# 03_MSP430_AFE.net
KiCad netlist of a schematic drawn in Altium Designer
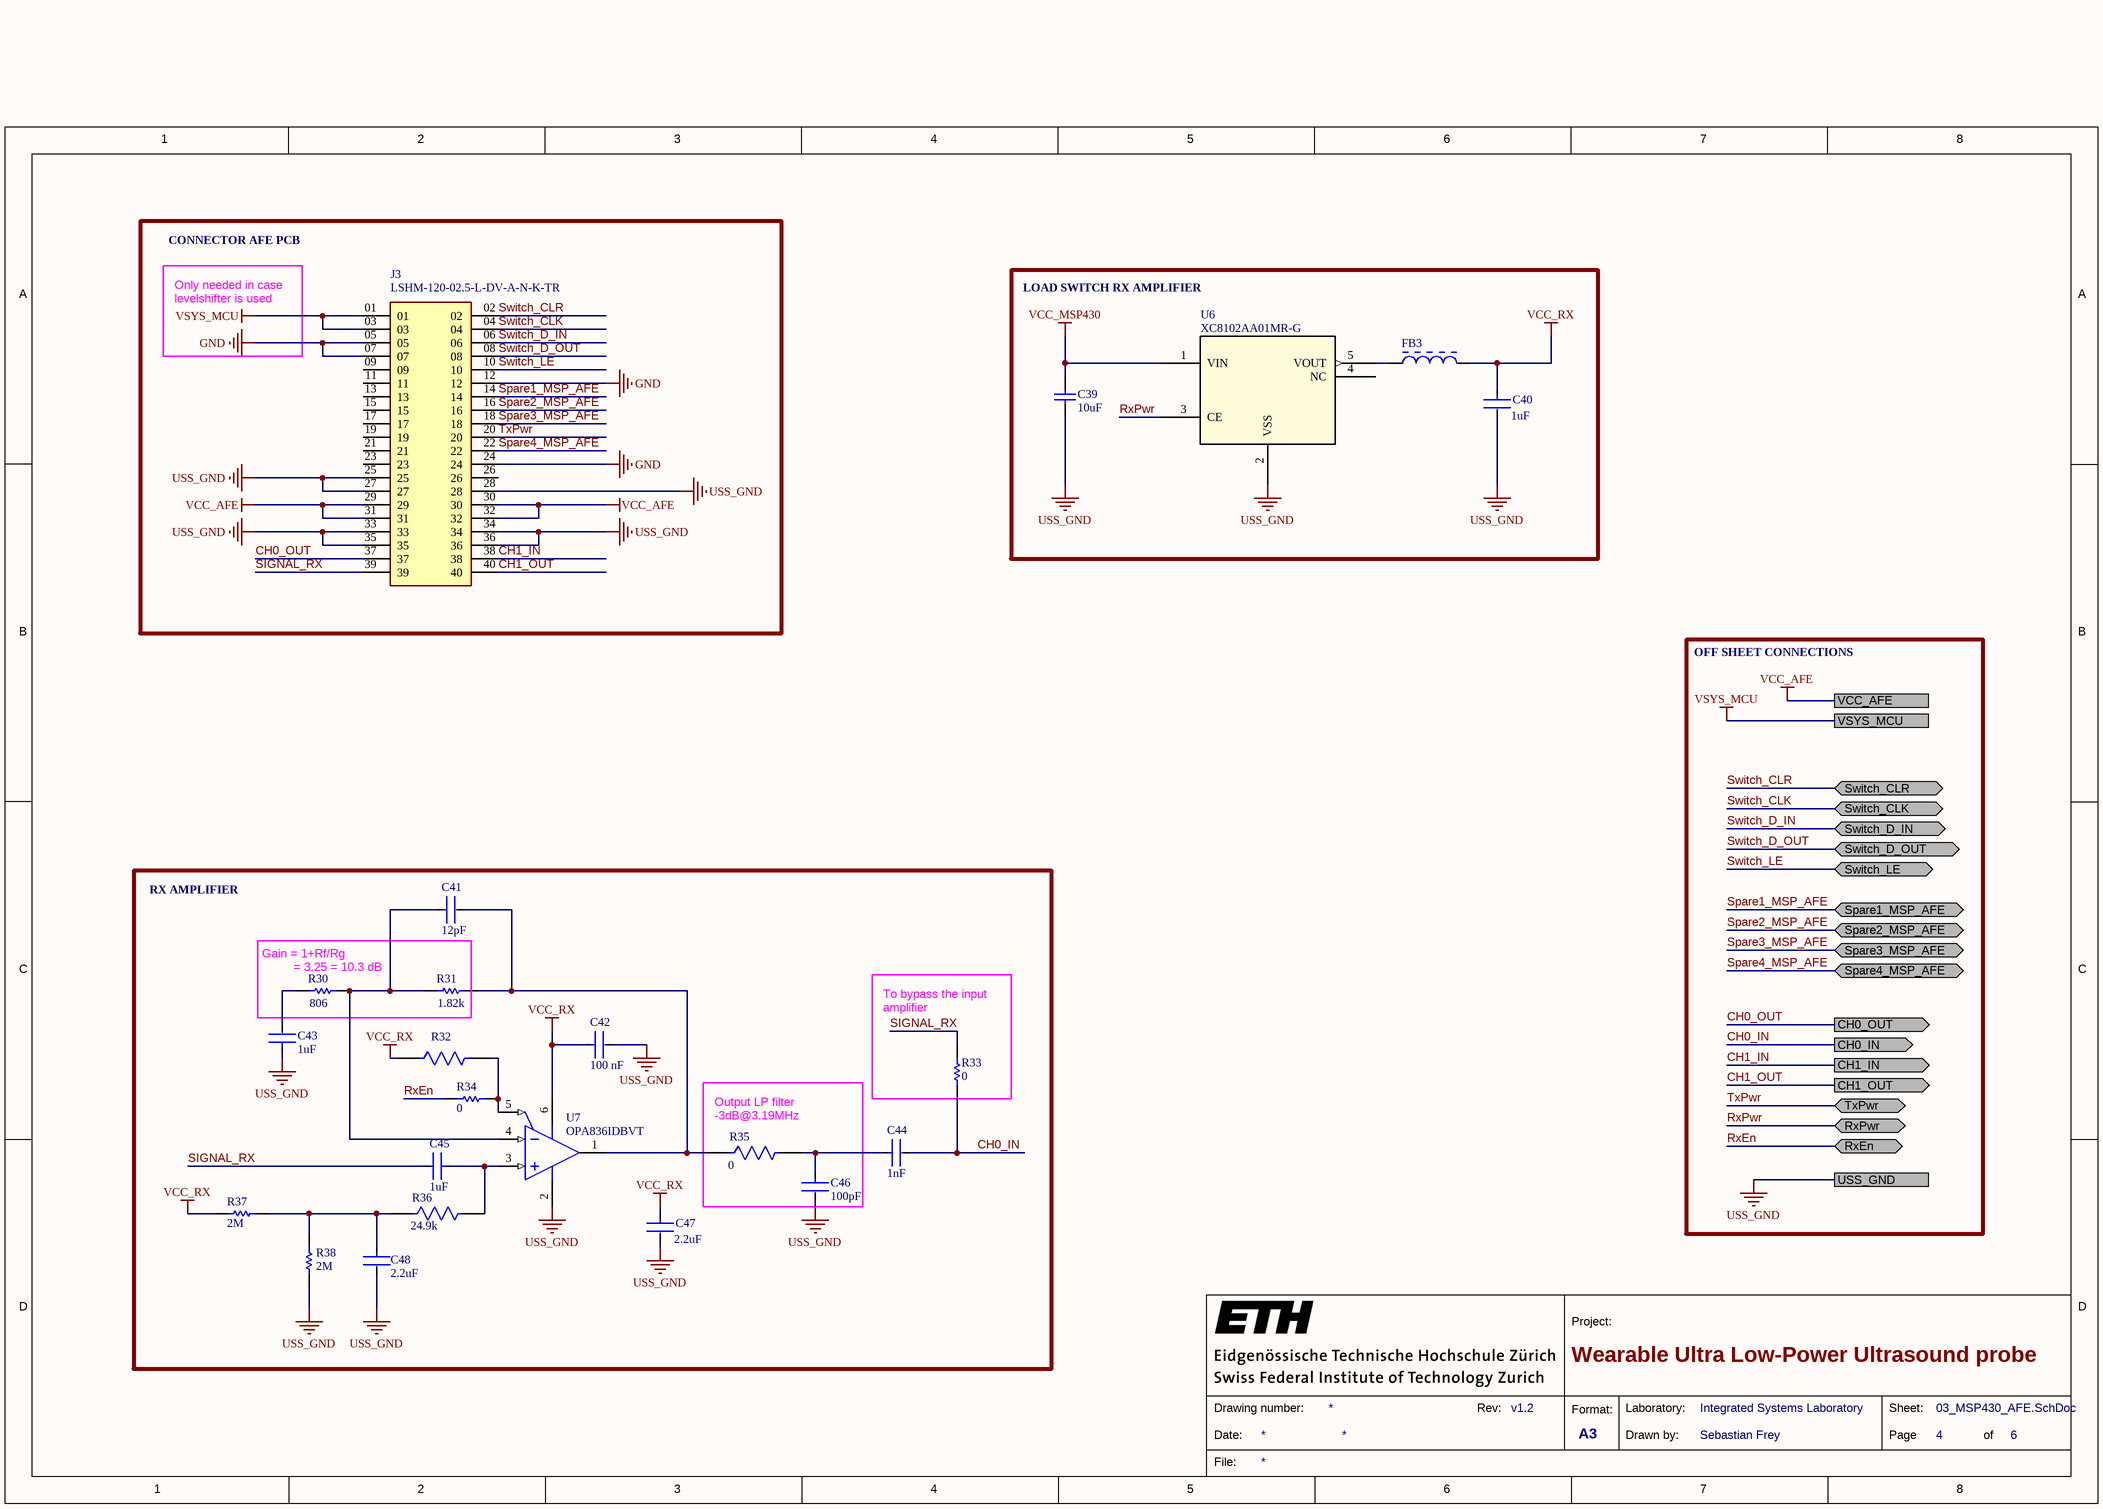
[diagram p0: 03_MSP430_AFE.SchDoc]

(export (version "E")
  (design (tool "Eeschema 10.0.6"))
  (components
    (comp (ref "C39")
      (value "10uF")
      (footprint "CAPC0603(1608)100_L")
      (description "CAP 10uF 10V ±10% 0603 (1608 Metric) Thickness 1mm SMD")
      (fields (field (name "TOLERANCE") "Â±10%") (field (name "Comment") "C1608X5R1A106K080AC"))
      (libsource (lib "Altium Content Vault") (part "CMP-1035-02799-1"))
    )
    (comp (ref "C40")
      (value "C1608X7R1C105K080AC")
      (footprint "FP-C1608-080-0_1-IPC_B")
      (description "Multilayer Ceramic Capacitors 1μF ±10% 16V X7R SMD 0603")
      (fields
        (field (name "VOLTAGE") "16V")
        (field (name "CAPACITANCE") "1uF")
        (field (name "TOLERANCE") "10%")
      )
      (libsource (lib "Altium Content Vault") (part "236180d848d6139a670b325ea6854c9"))
    )
    (comp (ref "C41")
      (value "GJM1555C1H120GB01D")
      (footprint "FP-GJM155-0_05-IPC_A")
      (description "Multi-Layer Ceramic Capacitor 12pF C0G  ±2% 0402 Paper T/R")
      (fields (field (name "TOLERANCE") "2%") (field (name "CAPACITANCE") "12pF"))
      (libsource (lib "Altium Content Vault") (part "02cd4be3c70576c341d710602a673aa"))
    )
    (comp (ref "C42")
      (value "100 nF")
      (footprint "FP-CC0402-MFG")
      (description "CAP CER 0.1UF 16V X7R 0402")
      (fields (field (name "MANUFACTURER") "YAGEO") (field (name "TOLERANCE") "0.1"))
      (libsource (lib "Altium Content Vault") (part "11868f565c42a9108669ba33697ecf6"))
    )
    (comp (ref "C43")
      (value "C1608X7R1C105K080AC")
      (footprint "FP-C1608-080-0_1-IPC_B")
      (description "Multilayer Ceramic Capacitors 1μF ±10% 16V X7R SMD 0603")
      (fields
        (field (name "VOLTAGE") "16V")
        (field (name "CAPACITANCE") "1uF")
        (field (name "TOLERANCE") "10%")
      )
      (libsource (lib "Altium Content Vault") (part "236180d848d6139a670b325ea6854c9"))
    )
    (comp (ref "C44")
      (value "GRM1555C1H102JA01D")
      (footprint "FP-GRM155-0_05-IPC_B")
      (description "Chip Multilayer Ceramic Capacitors for General Purpose, 0402, 1000pF, C0G, 30ppm/°C, 5%, 50V")
      (fields
        (field (name "TOLERANCE") "5%")
        (field (name "VOLTAGE") "50V")
        (field (name "CAPACITANCE") "1nF")
      )
      (libsource (lib "Altium Content Vault") (part "02cd4be3c70576c341d710602a673aa"))
    )
    (comp (ref "C45")
      (value "C1608X7R1C105K080AC")
      (footprint "FP-C1608-080-0_1-IPC_B")
      (description "Multilayer Ceramic Capacitors 1μF ±10% 16V X7R SMD 0603")
      (fields
        (field (name "VOLTAGE") "16V")
        (field (name "CAPACITANCE") "1uF")
        (field (name "TOLERANCE") "10%")
      )
      (libsource (lib "Altium Content Vault") (part "236180d848d6139a670b325ea6854c9"))
    )
    (comp (ref "C46")
      (value "04025A101JAT2A")
      (footprint "FP-04025A101JAT2A-MFG")
      (description "CAP CER 100PF 50V C0G/NP0 0402")
      (fields
        (field (name "TOLERANCE") "5%")
        (field (name "VOLTAGE") "50V")
        (field (name "CAPACITANCE") "100pF")
      )
      (libsource (lib "Altium Content Vault") (part "f23184f103b6ebe33a8c269c53dcba6"))
    )
    (comp (ref "C47")
      (value "GRM188R61C225KE15D")
      (footprint "FP-CGA3E-0_3-0_1-MFG")
      (description "Cap Ceramic 2.2uF 16V X5R 10% Pad SMD 0603 +85°C Automotive T/R")
      (fields (field (name "TOLERANCE") "10%") (field (name "CAPACITANCE") "2.2uF"))
      (libsource (lib "Altium Content Vault") (part "b4654b650e69147ec39a6b967a45e02"))
    )
    (comp (ref "C48")
      (value "GRM188R61C225KE15D")
      (footprint "FP-CGA3E-0_3-0_1-MFG")
      (description "Cap Ceramic 2.2uF 16V X5R 10% Pad SMD 0603 +85°C Automotive T/R")
      (fields (field (name "TOLERANCE") "10%") (field (name "CAPACITANCE") "2.2uF"))
      (libsource (lib "Altium Content Vault") (part "b4654b650e69147ec39a6b967a45e02"))
    )
    (comp (ref "FB3")
      (value "BLM03AX800SN1D")
      (footprint "MURA-BLM03-CHIP-2_V")
      (fields (field (name "MANUFACTURER") "Murata") (field (name "TOLERANCE") "25%"))
      (libsource (lib "Altium Content Vault") (part "MURA-FB-2"))
    )
    (comp (ref "J3")
      (value "LSHM-120-02.5-L-DV-A-N-K-TR")
      (footprint "PcbLib1:SAMTEC_LSHM-120-XX.X-X-DV-A-N-XX")
      (description "Conn Socket and Terminal Strip HDR/SKT 40 POS 0.5mm Solder ST SMD T/R")
      (fields
        (field (name "MANUFACTURER") "Samtec")
        (field (name "MANUFACTURER PART NUMBER") "LSHM-120-02.5-L-DV-A-N-K-TR")
      )
      (libsource (lib "Schlib1") (part "LSHM-120-02.5-L-DV-A-N-K-TR"))
    )
    (comp (ref "R30")
      (value "RC0603FR-07806RL")
      (footprint "RESC1608X55X25LL10T15")
      (fields (field (name "MANUFACTURER") "Yageo") (field (name "RESISTANCE") "806"))
      (libsource (lib "Altium Content Vault") (part "RES"))
    )
    (comp (ref "R31")
      (value "RC0603FR-071K82L")
      (footprint "RESC1608X55X25ML10T15")
      (fields (field (name "MANUFACTURER") "Yageo") (field (name "RESISTANCE") "1.82k"))
      (libsource (lib "Altium Content Vault") (part "RES"))
    )
    (comp (ref "R32")
      (value "TNPW040210K0BEED")
      (footprint "FP-TNPW0402-e3-MFG")
      (description "RES 10K OHM 0.1% 1/10W 0402")
      (fields
        (field (name "TOLERANCE") "0.1%")
        (field (name "OCTOPART") "https://octopart.com/tnpw040210k0beed-vishay-41229038")
      )
      (libsource (lib "Altium Content Vault") (part "1029c3af85768c4190bb7ad29bc67b5"))
    )
    (comp (ref "R33")
      (value "RC0402JR-070RL")
      (footprint "RESC1005X40X25NL05T10")
      (fields (field (name "MANUFACTURER") "Yageo / Phycomp") (field (name "RESISTANCE") "0"))
      (libsource (lib "Altium Content Vault") (part "RES"))
    )
    (comp (ref "R34")
      (value "RC0402JR-070RL")
      (footprint "RESC1005X40X25NL05T10")
      (fields (field (name "MANUFACTURER") "Yageo / Phycomp") (field (name "RESISTANCE") "0"))
      (libsource (lib "Altium Content Vault") (part "RES"))
    )
    (comp (ref "R35")
      (value "CR0402-J/-000GLF")
      (footprint "FP-CR0402-IPC_B")
      (description "Thick Film Chip Resistors 0402 0Ω 0.0625W 5%")
      (fields (field (name "TOLERANCE") "5%") (field (name "RESISTANCE") "0"))
      (libsource (lib "Altium Content Vault") (part "1029c3af85768c4190bb7ad29bc67b5"))
    )
    (comp (ref "R36")
      (value "RC0603FR-0724K9L")
      (footprint "FP-RC_L0603-MFG")
      (description "RES SMD 24.9K OHM 1% 1/10W 0603")
      (fields
        (field (name "VOLTAGE") "75V")
        (field (name "MANUFACTURER") "Yageo")
        (field (name "RESISTANCE") "24.9k")
      )
      (libsource (lib "Altium Content Vault") (part "1029c3af85768c4190bb7ad29bc67b5"))
    )
    (comp (ref "R37")
      (value "RC0603FR-072ML")
      (footprint "RESC1608X55X30LL15T15")
      (fields (field (name "MANUFACTURER") "YAEGO") (field (name "PARAMETER 1") "2M"))
      (libsource (lib "Altium Content Vault") (part "RES"))
    )
    (comp (ref "R38")
      (value "RC0603FR-072ML")
      (footprint "RESC1608X55X30LL15T15")
      (fields (field (name "MANUFACTURER") "YAEGO") (field (name "PARAMETER 1") "2M"))
      (libsource (lib "Altium Content Vault") (part "RES"))
    )
    (comp (ref "U6")
      (value "XC8102AA01MR-G")
      (footprint "PcbLib1:XC8102_SOT-25_TOR")
      (description "No Description Available")
      (fields (field (name "COPYRIGHT") "Copyright (C) 2021 Ultra Librarian. All rights reserved."))
      (libsource (lib "Schlib1") (part "XC8102AA01MR-G"))
    )
    (comp (ref "U7")
      (value "OPA836IDBVT")
      (footprint "DBV0006A_L")
      (fields (field (name "MANUFACTURER") "Texas Instruments"))
      (libsource (lib "Altium Content Vault") (part "TI-OPA83XDBV6"))
    )
  )
  (nets
    (net (code "1") (name "/CH0_IN") (class "Default")
      (node (ref "C44") (pin "2") (pinfunction "2_2") (pintype "passive"))
      (node (ref "R33") (pin "1") (pinfunction "1_1") (pintype "passive"))
    )
    (net (code "2") (name "/CH0_OUT") (class "Default")
      (node (ref "J3") (pin "37") (pinfunction "37_37") (pintype "passive"))
    )
    (net (code "3") (name "/CH1_IN") (class "Default")
      (node (ref "J3") (pin "38") (pinfunction "38_38") (pintype "passive"))
    )
    (net (code "4") (name "/CH1_OUT") (class "Default")
      (node (ref "J3") (pin "40") (pinfunction "40_40") (pintype "passive"))
    )
    (net (code "5") (name "/RxEn") (class "Default")
      (node (ref "R34") (pin "2") (pinfunction "2_2") (pintype "passive"))
    )
    (net (code "6") (name "/RxPwr") (class "Default")
      (node (ref "U6") (pin "3") (pinfunction "CE_3") (pintype "passive"))
    )
    (net (code "7") (name "/SIGNAL_RX") (class "Default")
      (node (ref "C45") (pin "1") (pinfunction "1_1") (pintype "passive"))
      (node (ref "J3") (pin "39") (pinfunction "39_39") (pintype "passive"))
      (node (ref "R33") (pin "2") (pinfunction "2_2") (pintype "passive"))
    )
    (net (code "8") (name "/Spare1_MSP_AFE") (class "Default")
      (node (ref "J3") (pin "14") (pinfunction "14_14") (pintype "passive"))
    )
    (net (code "9") (name "/Spare2_MSP_AFE") (class "Default")
      (node (ref "J3") (pin "16") (pinfunction "16_16") (pintype "passive"))
    )
    (net (code "10") (name "/Spare3_MSP_AFE") (class "Default")
      (node (ref "J3") (pin "18") (pinfunction "18_18") (pintype "passive"))
    )
    (net (code "11") (name "/Spare4_MSP_AFE") (class "Default")
      (node (ref "J3") (pin "22") (pinfunction "22_22") (pintype "passive"))
    )
    (net (code "12") (name "/Switch_CLK") (class "Default")
      (node (ref "J3") (pin "04") (pinfunction "04_04") (pintype "passive"))
    )
    (net (code "13") (name "/Switch_CLR") (class "Default")
      (node (ref "J3") (pin "02") (pinfunction "02_02") (pintype "passive"))
    )
    (net (code "14") (name "/Switch_D_IN") (class "Default")
      (node (ref "J3") (pin "06") (pinfunction "06_06") (pintype "passive"))
    )
    (net (code "15") (name "/Switch_D_OUT") (class "Default")
      (node (ref "J3") (pin "08") (pinfunction "08_08") (pintype "passive"))
    )
    (net (code "16") (name "/Switch_LE") (class "Default")
      (node (ref "J3") (pin "10") (pinfunction "10_10") (pintype "passive"))
    )
    (net (code "17") (name "/TxPwr") (class "Default")
      (node (ref "J3") (pin "20") (pinfunction "20_20") (pintype "passive"))
    )
    (net (code "18") (name "GND") (class "Default")
      (node (ref "J3") (pin "05") (pinfunction "05_05") (pintype "passive"))
      (node (ref "J3") (pin "07") (pinfunction "07_07") (pintype "passive"))
      (node (ref "J3") (pin "12") (pinfunction "12_12") (pintype "passive"))
      (node (ref "J3") (pin "24") (pinfunction "24_24") (pintype "passive"))
    )
    (net (code "19") (name "Net-(C43-Pad1)") (class "Default")
      (node (ref "C43") (pin "1") (pinfunction "1_1") (pintype "passive"))
      (node (ref "R30") (pin "1") (pinfunction "1_1") (pintype "passive"))
    )
    (net (code "20") (name "Net-(C44-Pad1)") (class "Default")
      (node (ref "C44") (pin "1") (pinfunction "1_1") (pintype "passive"))
      (node (ref "C46") (pin "2") (pinfunction "2_2") (pintype "passive"))
      (node (ref "R35") (pin "2") (pinfunction "2_2") (pintype "passive"))
    )
    (net (code "21") (name "Net-(C48-Pad1)") (class "Default")
      (node (ref "C48") (pin "1") (pinfunction "1_1") (pintype "passive"))
      (node (ref "R36") (pin "1") (pinfunction "1_1") (pintype "passive"))
      (node (ref "R37") (pin "1") (pinfunction "1_1") (pintype "passive"))
      (node (ref "R38") (pin "2") (pinfunction "2_2") (pintype "passive"))
    )
    (net (code "22") (name "Net-(U6-VOUT)") (class "Default")
      (node (ref "FB3") (pin "1") (pinfunction "1_1") (pintype "passive"))
      (node (ref "U6") (pin "5") (pinfunction "VOUT_5") (pintype "output"))
    )
    (net (code "23") (name "Net-(U7-VIN+)") (class "Default")
      (node (ref "C45") (pin "2") (pinfunction "2_2") (pintype "passive"))
      (node (ref "R36") (pin "2") (pinfunction "2_2") (pintype "passive"))
      (node (ref "U7") (pin "3") (pinfunction "VIN+_3") (pintype "input"))
    )
    (net (code "24") (name "Net-(U7-VIN-)") (class "Default")
      (node (ref "C41") (pin "1") (pinfunction "1_1") (pintype "passive"))
      (node (ref "R30") (pin "2") (pinfunction "2_2") (pintype "passive"))
      (node (ref "R31") (pin "1") (pinfunction "1_1") (pintype "passive"))
      (node (ref "U7") (pin "4") (pinfunction "VIN-_4") (pintype "input"))
    )
    (net (code "25") (name "Net-(U7-VOUT)") (class "Default")
      (node (ref "C41") (pin "2") (pinfunction "2_2") (pintype "passive"))
      (node (ref "R31") (pin "2") (pinfunction "2_2") (pintype "passive"))
      (node (ref "R35") (pin "1") (pinfunction "1_1") (pintype "passive"))
      (node (ref "U7") (pin "1") (pinfunction "VOUT_1") (pintype "tri_state"))
    )
    (net (code "26") (name "Net-(U7-~{PD})") (class "Default")
      (node (ref "R32") (pin "2") (pinfunction "2_2") (pintype "passive"))
      (node (ref "R34") (pin "1") (pinfunction "1_1") (pintype "passive"))
      (node (ref "U7") (pin "5") (pinfunction "~{PD}_5") (pintype "input"))
    )
    (net (code "27") (name "USS_GND") (class "Default")
      (node (ref "C39") (pin "1") (pinfunction "1_1") (pintype "passive"))
      (node (ref "C40") (pin "1") (pinfunction "1_1") (pintype "passive"))
      (node (ref "C42") (pin "2") (pinfunction "2_2") (pintype "passive"))
      (node (ref "C43") (pin "2") (pinfunction "2_2") (pintype "passive"))
      (node (ref "C46") (pin "1") (pinfunction "1_1") (pintype "passive"))
      (node (ref "C47") (pin "2") (pinfunction "2_2") (pintype "passive"))
      (node (ref "C48") (pin "2") (pinfunction "2_2") (pintype "passive"))
      (node (ref "J3") (pin "25") (pinfunction "25_25") (pintype "passive"))
      (node (ref "J3") (pin "27") (pinfunction "27_27") (pintype "passive"))
      (node (ref "J3") (pin "28") (pinfunction "28_28") (pintype "passive"))
      (node (ref "J3") (pin "33") (pinfunction "33_33") (pintype "passive"))
      (node (ref "J3") (pin "34") (pinfunction "34_34") (pintype "passive"))
      (node (ref "J3") (pin "35") (pinfunction "35_35") (pintype "passive"))
      (node (ref "J3") (pin "36") (pinfunction "36_36") (pintype "passive"))
      (node (ref "R38") (pin "1") (pinfunction "1_1") (pintype "passive"))
      (node (ref "U6") (pin "2") (pinfunction "VSS_2") (pintype "passive"))
      (node (ref "U7") (pin "2") (pinfunction "VS-_2") (pintype "power_in"))
    )
    (net (code "28") (name "VCC_AFE") (class "Default")
      (node (ref "J3") (pin "29") (pinfunction "29_29") (pintype "passive"))
      (node (ref "J3") (pin "30") (pinfunction "30_30") (pintype "passive"))
      (node (ref "J3") (pin "31") (pinfunction "31_31") (pintype "passive"))
      (node (ref "J3") (pin "32") (pinfunction "32_32") (pintype "passive"))
    )
    (net (code "29") (name "VCC_MSP430") (class "Default")
      (node (ref "C39") (pin "2") (pinfunction "2_2") (pintype "passive"))
      (node (ref "U6") (pin "1") (pinfunction "VIN_1") (pintype "power_in"))
    )
    (net (code "30") (name "VCC_RX") (class "Default")
      (node (ref "C40") (pin "2") (pinfunction "2_2") (pintype "passive"))
      (node (ref "C42") (pin "1") (pinfunction "1_1") (pintype "passive"))
      (node (ref "C47") (pin "1") (pinfunction "1_1") (pintype "passive"))
      (node (ref "FB3") (pin "2") (pinfunction "2_2") (pintype "passive"))
      (node (ref "R32") (pin "1") (pinfunction "1_1") (pintype "passive"))
      (node (ref "R37") (pin "2") (pinfunction "2_2") (pintype "passive"))
      (node (ref "U7") (pin "6") (pinfunction "VS+_6") (pintype "power_in"))
    )
    (net (code "31") (name "VSYS_MCU") (class "Default")
      (node (ref "J3") (pin "01") (pinfunction "01_01") (pintype "passive"))
      (node (ref "J3") (pin "03") (pinfunction "03_03") (pintype "passive"))
    )
    (net (code "32") (name "unconnected-(J3-Pad09)") (class "Default")
      (node (ref "J3") (pin "09") (pinfunction "09_09") (pintype "passive"))
    )
    (net (code "33") (name "unconnected-(J3-Pad11)") (class "Default")
      (node (ref "J3") (pin "11") (pinfunction "11_11") (pintype "passive"))
    )
    (net (code "34") (name "unconnected-(J3-Pad13)") (class "Default")
      (node (ref "J3") (pin "13") (pinfunction "13_13") (pintype "passive"))
    )
    (net (code "35") (name "unconnected-(J3-Pad15)") (class "Default")
      (node (ref "J3") (pin "15") (pinfunction "15_15") (pintype "passive"))
    )
    (net (code "36") (name "unconnected-(J3-Pad17)") (class "Default")
      (node (ref "J3") (pin "17") (pinfunction "17_17") (pintype "passive"))
    )
    (net (code "37") (name "unconnected-(J3-Pad19)") (class "Default")
      (node (ref "J3") (pin "19") (pinfunction "19_19") (pintype "passive"))
    )
    (net (code "38") (name "unconnected-(J3-Pad21)") (class "Default")
      (node (ref "J3") (pin "21") (pinfunction "21_21") (pintype "passive"))
    )
    (net (code "39") (name "unconnected-(J3-Pad23)") (class "Default")
      (node (ref "J3") (pin "23") (pinfunction "23_23") (pintype "passive"))
    )
    (net (code "40") (name "unconnected-(J3-Pad26)") (class "Default")
      (node (ref "J3") (pin "26") (pinfunction "26_26") (pintype "passive"))
    )
    (net (code "41") (name "unconnected-(U6-NC-Pad4)") (class "Default")
      (node (ref "U6") (pin "4") (pinfunction "NC_4") (pintype "passive"))
    )
  )
)
